# DDR3A.net
KiCad netlist of a schematic drawn in Altium Designer
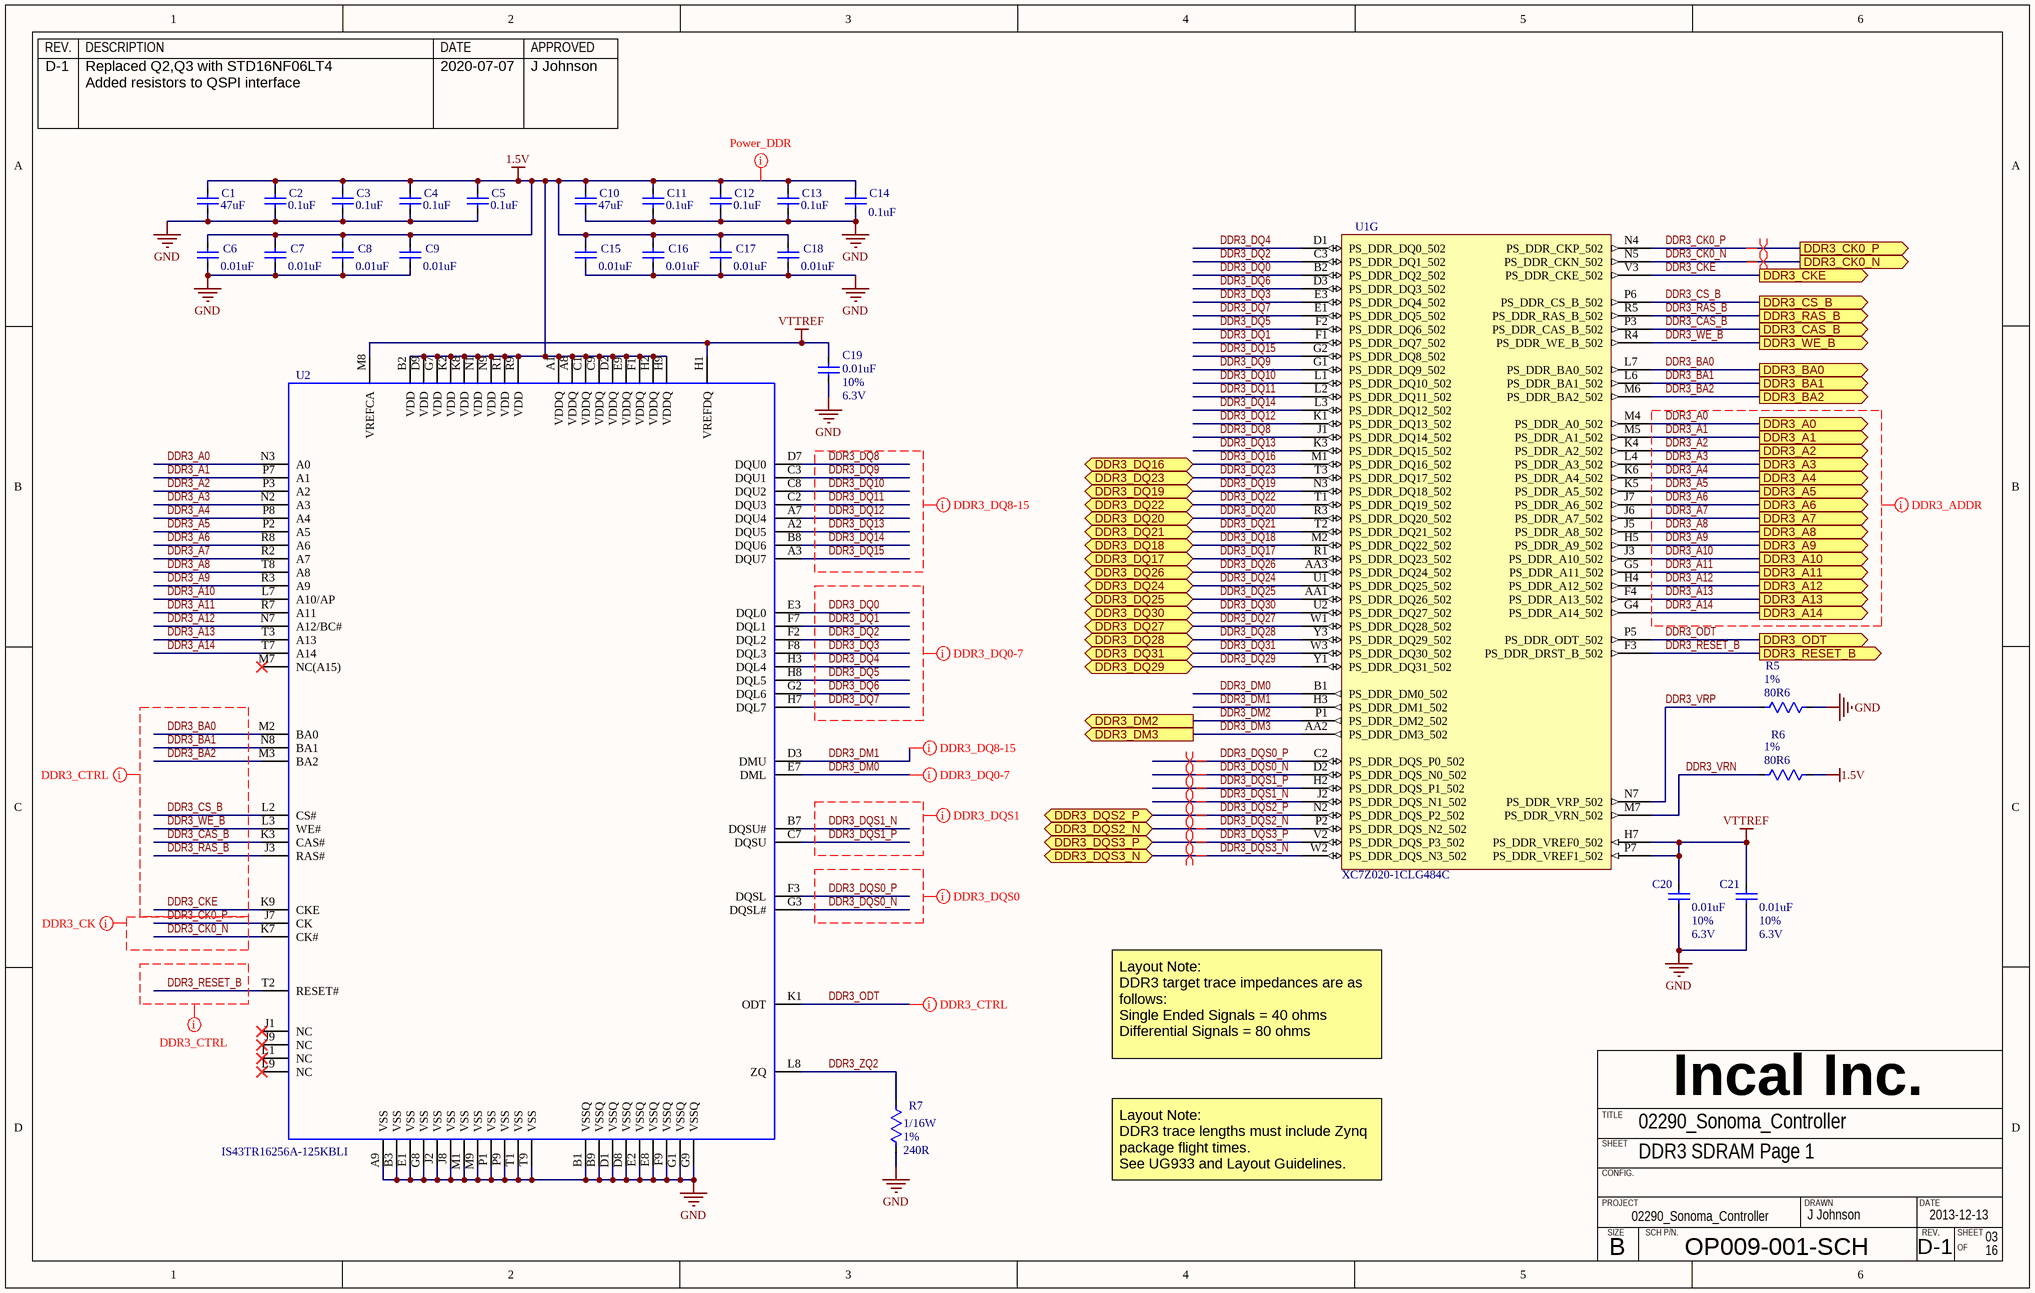
[diagram p0: DDR3A.SchDoc]

(export (version "E")
  (design (tool "Eeschema 10.0.6"))
  (components
    (comp (ref "C1")
      (value "47uF")
      (footprint "CAPC2013X125N")
      (description "Capacitor ceramic, X5R, 47uF, 6.3V, 20%, -55 to +85 C,")
      (fields (field (name "TOLERANCE") "20%") (field (name "VOLTAGE") "6.3V"))
      (libsource (lib "parts") (part "CAPACITOR_NP_TYPE1"))
    )
    (comp (ref "C2")
      (value "0.1uF")
      (footprint "CAPC0603X33N")
      (description "Capacitor ceramic, X5R, 0.1uF, 6.3V, 10%, -55 to +125 C, EIA0201")
      (fields (field (name "TOLERANCE") "10%") (field (name "VOLTAGE") "6.3V"))
      (libsource (lib "parts") (part "CAPACITOR_NP_TYPE1"))
    )
    (comp (ref "C3")
      (value "0.1uF")
      (footprint "CAPC0603X33N")
      (description "Capacitor ceramic, X5R, 0.1uF, 6.3V, 10%, -55 to +125 C, EIA0201")
      (fields (field (name "TOLERANCE") "10%") (field (name "VOLTAGE") "6.3V"))
      (libsource (lib "parts") (part "CAPACITOR_NP_TYPE1"))
    )
    (comp (ref "C4")
      (value "0.1uF")
      (footprint "CAPC0603X33N")
      (description "Capacitor ceramic, X5R, 0.1uF, 6.3V, 10%, -55 to +125 C, EIA0201")
      (fields (field (name "TOLERANCE") "10%") (field (name "VOLTAGE") "6.3V"))
      (libsource (lib "parts") (part "CAPACITOR_NP_TYPE1"))
    )
    (comp (ref "C5")
      (value "0.1uF")
      (footprint "CAPC0603X33N")
      (description "Capacitor ceramic, X5R, 0.1uF, 6.3V, 10%, -55 to +125 C, EIA0201")
      (fields (field (name "TOLERANCE") "10%") (field (name "VOLTAGE") "6.3V"))
      (libsource (lib "parts") (part "CAPACITOR_NP_TYPE1"))
    )
    (comp (ref "C6")
      (value "0.01uF")
      (footprint "CAPC0603X33N")
      (description "Capacitor ceramic, X5R, 0.01uF, 6.3V, 10%, -55 to +125 C, EIA0201")
      (fields (field (name "TOLERANCE") "10%") (field (name "VOLTAGE") "6.3V"))
      (libsource (lib "parts") (part "CAPACITOR_NP_TYPE1"))
    )
    (comp (ref "C7")
      (value "0.01uF")
      (footprint "CAPC0603X33N")
      (description "Capacitor ceramic, X5R, 0.01uF, 6.3V, 10%, -55 to +125 C, EIA0201")
      (fields (field (name "TOLERANCE") "10%") (field (name "VOLTAGE") "6.3V"))
      (libsource (lib "parts") (part "CAPACITOR_NP_TYPE1"))
    )
    (comp (ref "C8")
      (value "0.01uF")
      (footprint "CAPC0603X33N")
      (description "Capacitor ceramic, X5R, 0.01uF, 6.3V, 10%, -55 to +125 C, EIA0201")
      (fields (field (name "TOLERANCE") "10%") (field (name "VOLTAGE") "6.3V"))
      (libsource (lib "parts") (part "CAPACITOR_NP_TYPE1"))
    )
    (comp (ref "C9")
      (value "0.01uF")
      (footprint "CAPC0603X33N")
      (description "Capacitor ceramic, X5R, 0.01uF, 6.3V, 10%, -55 to +125 C, EIA0201")
      (fields (field (name "TOLERANCE") "10%") (field (name "VOLTAGE") "6.3V"))
      (libsource (lib "parts") (part "CAPACITOR_NP_TYPE1"))
    )
    (comp (ref "C10")
      (value "47uF")
      (footprint "CAPC2013X125N")
      (description "Capacitor ceramic, X5R, 47uF, 6.3V, 20%, -55 to +85 C,")
      (fields (field (name "TOLERANCE") "20%") (field (name "VOLTAGE") "6.3V"))
      (libsource (lib "parts") (part "CAPACITOR_NP_TYPE1"))
    )
    (comp (ref "C11")
      (value "0.1uF")
      (footprint "CAPC0603X33N")
      (description "Capacitor ceramic, X5R, 0.1uF, 6.3V, 10%, -55 to +125 C, EIA0201")
      (fields (field (name "TOLERANCE") "10%") (field (name "VOLTAGE") "6.3V"))
      (libsource (lib "parts") (part "CAPACITOR_NP_TYPE1"))
    )
    (comp (ref "C12")
      (value "0.1uF")
      (footprint "CAPC0603X33N")
      (description "Capacitor ceramic, X5R, 0.1uF, 6.3V, 10%, -55 to +125 C, EIA0201")
      (fields (field (name "TOLERANCE") "10%") (field (name "VOLTAGE") "6.3V"))
      (libsource (lib "parts") (part "CAPACITOR_NP_TYPE1"))
    )
    (comp (ref "C13")
      (value "0.1uF")
      (footprint "CAPC0603X33N")
      (description "Capacitor ceramic, X5R, 0.1uF, 6.3V, 10%, -55 to +125 C, EIA0201")
      (fields (field (name "TOLERANCE") "10%") (field (name "VOLTAGE") "6.3V"))
      (libsource (lib "parts") (part "CAPACITOR_NP_TYPE1"))
    )
    (comp (ref "C14")
      (value "0.1uF")
      (footprint "CAPC0603X33N")
      (description "Capacitor ceramic, X5R, 0.1uF, 6.3V, 10%, -55 to +125 C, EIA0201")
      (fields (field (name "TOLERANCE") "10%") (field (name "VOLTAGE") "6.3V"))
      (libsource (lib "parts") (part "CAPACITOR_NP_TYPE1"))
    )
    (comp (ref "C15")
      (value "0.01uF")
      (footprint "CAPC0603X33N")
      (description "Capacitor ceramic, X5R, 0.01uF, 6.3V, 10%, -55 to +125 C, EIA0201")
      (fields (field (name "TOLERANCE") "10%") (field (name "VOLTAGE") "6.3V"))
      (libsource (lib "parts") (part "CAPACITOR_NP_TYPE1"))
    )
    (comp (ref "C16")
      (value "0.01uF")
      (footprint "CAPC0603X33N")
      (description "Capacitor ceramic, X5R, 0.01uF, 6.3V, 10%, -55 to +125 C, EIA0201")
      (fields (field (name "TOLERANCE") "10%") (field (name "VOLTAGE") "6.3V"))
      (libsource (lib "parts") (part "CAPACITOR_NP_TYPE1"))
    )
    (comp (ref "C17")
      (value "0.01uF")
      (footprint "CAPC0603X33N")
      (description "Capacitor ceramic, X5R, 0.01uF, 6.3V, 10%, -55 to +125 C, EIA0201")
      (fields (field (name "TOLERANCE") "10%") (field (name "VOLTAGE") "6.3V"))
      (libsource (lib "parts") (part "CAPACITOR_NP_TYPE1"))
    )
    (comp (ref "C18")
      (value "0.01uF")
      (footprint "CAPC0603X33N")
      (description "Capacitor ceramic, X5R, 0.01uF, 6.3V, 10%, -55 to +125 C, EIA0201")
      (fields (field (name "TOLERANCE") "10%") (field (name "VOLTAGE") "6.3V"))
      (libsource (lib "parts") (part "CAPACITOR_NP_TYPE1"))
    )
    (comp (ref "C19")
      (value "0.01uF")
      (footprint "CAPC0603X33N")
      (description "Capacitor ceramic, X5R, 0.01uF, 6.3V, 10%, -55 to +125 C, EIA0201")
      (fields
        (field (name "TOLERANCE") "10%")
        (field (name "VOLTAGE") "6.3V")
        (field (name "Comment") "CAPACITOR_NP_TYPE1")
      )
      (libsource (lib "parts") (part "CAPACITOR_NP_TYPE1"))
    )
    (comp (ref "C20")
      (value "0.01uF")
      (footprint "CAPC0603X33N")
      (description "Capacitor ceramic, X5R, 0.01uF, 6.3V, 10%, -55 to +125 C, EIA0201")
      (fields
        (field (name "TOLERANCE") "10%")
        (field (name "VOLTAGE") "6.3V")
        (field (name "Comment") "CAPACITOR_NP_TYPE1")
      )
      (libsource (lib "parts") (part "CAPACITOR_NP_TYPE1"))
    )
    (comp (ref "C21")
      (value "0.01uF")
      (footprint "CAPC0603X33N")
      (description "Capacitor ceramic, X5R, 0.01uF, 6.3V, 10%, -55 to +125 C, EIA0201")
      (fields
        (field (name "TOLERANCE") "10%")
        (field (name "VOLTAGE") "6.3V")
        (field (name "Comment") "CAPACITOR_NP_TYPE1")
      )
      (libsource (lib "parts") (part "CAPACITOR_NP_TYPE1"))
    )
    (comp (ref "R5")
      (value "80R6")
      (footprint "RESC1005X33N")
      (description "Resistor, 80R6, 1/16W, 1%, -50 to +155 C, EIA0402, EIA(M)1005")
      (fields (field (name "VOLTAGE") "50V") (field (name "POWER") "1/16W") (field (name "TOLERANCE") "1%"))
      (libsource (lib "parts") (part "RESISTOR_TYPE1"))
    )
    (comp (ref "R6")
      (value "80R6")
      (footprint "RESC1005X33N")
      (description "Resistor, 80R6, 1/16W, 1%, -50 to +155 C, EIA0402, EIA(M)1005")
      (fields (field (name "VOLTAGE") "50V") (field (name "POWER") "1/16W") (field (name "TOLERANCE") "1%"))
      (libsource (lib "parts") (part "RESISTOR_TYPE1"))
    )
    (comp (ref "R7")
      (value "240R")
      (footprint "RESC1005X33N")
      (description "Resistor, 240R, 1/16W, 1%, -50 to +155 C, EIA0402, EIA(M)1005")
      (fields (field (name "VOLTAGE") "50V") (field (name "POWER") "1/16W") (field (name "TOLERANCE") "1%"))
      (libsource (lib "parts") (part "RESISTOR_TYPE1"))
    )
    (comp (ref "U1")
      (value "XC7Z020-1CLG484C")
      (footprint "CLG484")
      (description "667 MHz Zynq™-7000 AP SoC, 130 PS I/O, 200 FPGA I/O, 484-Ball BGA, Speed Grade 1, Commercial Grade")
      (fields (field (name "GENERIC PART NUMBER") "XC7Z020") (field (name "MANUFACTURER") "Xilinx"))
      (libsource (lib "parts") (part "XC7Z020-1CLG484C"))
    )
    (comp (ref "U2")
      (value "IS43TR16256A-125KBLI")
      (footprint "BGA96C80P6X16_900X1300X120")
      (description "DDR3 SDRAM, 512Mx8, 256Mx16 4Gb")
      (libsource (lib "parts") (part "IS43TR16256A-125KBLI"))
    )
  )
  (nets
    (net (code "1") (name "/DDR3_A0") (class "Default")
      (node (ref "U1") (pin "M4") (pinfunction "PS_DDR_A0_502_M4") (pintype "output"))
      (node (ref "U2") (pin "N3") (pinfunction "A0_N3") (pintype "passive"))
    )
    (net (code "2") (name "/DDR3_A1") (class "Default")
      (node (ref "U1") (pin "M5") (pinfunction "PS_DDR_A1_502_M5") (pintype "output"))
      (node (ref "U2") (pin "P7") (pinfunction "A1_P7") (pintype "passive"))
    )
    (net (code "3") (name "/DDR3_A2") (class "Default")
      (node (ref "U1") (pin "K4") (pinfunction "PS_DDR_A2_502_K4") (pintype "output"))
      (node (ref "U2") (pin "P3") (pinfunction "A2_P3") (pintype "passive"))
    )
    (net (code "4") (name "/DDR3_A3") (class "Default")
      (node (ref "U1") (pin "L4") (pinfunction "PS_DDR_A3_502_L4") (pintype "output"))
      (node (ref "U2") (pin "N2") (pinfunction "A3_N2") (pintype "passive"))
    )
    (net (code "5") (name "/DDR3_A4") (class "Default")
      (node (ref "U1") (pin "K6") (pinfunction "PS_DDR_A4_502_K6") (pintype "output"))
      (node (ref "U2") (pin "P8") (pinfunction "A4_P8") (pintype "passive"))
    )
    (net (code "6") (name "/DDR3_A5") (class "Default")
      (node (ref "U1") (pin "K5") (pinfunction "PS_DDR_A5_502_K5") (pintype "output"))
      (node (ref "U2") (pin "P2") (pinfunction "A5_P2") (pintype "passive"))
    )
    (net (code "7") (name "/DDR3_A6") (class "Default")
      (node (ref "U1") (pin "J7") (pinfunction "PS_DDR_A6_502_J7") (pintype "output"))
      (node (ref "U2") (pin "R8") (pinfunction "A6_R8") (pintype "passive"))
    )
    (net (code "8") (name "/DDR3_A7") (class "Default")
      (node (ref "U1") (pin "J6") (pinfunction "PS_DDR_A7_502_J6") (pintype "output"))
      (node (ref "U2") (pin "R2") (pinfunction "A7_R2") (pintype "passive"))
    )
    (net (code "9") (name "/DDR3_A8") (class "Default")
      (node (ref "U1") (pin "J5") (pinfunction "PS_DDR_A8_502_J5") (pintype "output"))
      (node (ref "U2") (pin "T8") (pinfunction "A8_T8") (pintype "passive"))
    )
    (net (code "10") (name "/DDR3_A9") (class "Default")
      (node (ref "U1") (pin "H5") (pinfunction "PS_DDR_A9_502_H5") (pintype "output"))
      (node (ref "U2") (pin "R3") (pinfunction "A9_R3") (pintype "passive"))
    )
    (net (code "11") (name "/DDR3_A10") (class "Default")
      (node (ref "U1") (pin "J3") (pinfunction "PS_DDR_A10_502_J3") (pintype "output"))
      (node (ref "U2") (pin "L7") (pinfunction "A10/AP_L7") (pintype "passive"))
    )
    (net (code "12") (name "/DDR3_A11") (class "Default")
      (node (ref "U1") (pin "G5") (pinfunction "PS_DDR_A11_502_G5") (pintype "output"))
      (node (ref "U2") (pin "R7") (pinfunction "A11_R7") (pintype "passive"))
    )
    (net (code "13") (name "/DDR3_A12") (class "Default")
      (node (ref "U1") (pin "H4") (pinfunction "PS_DDR_A12_502_H4") (pintype "output"))
      (node (ref "U2") (pin "N7") (pinfunction "A12/BC#_N7") (pintype "passive"))
    )
    (net (code "14") (name "/DDR3_A13") (class "Default")
      (node (ref "U1") (pin "F4") (pinfunction "PS_DDR_A13_502_F4") (pintype "output"))
      (node (ref "U2") (pin "T3") (pinfunction "A13_T3") (pintype "passive"))
    )
    (net (code "15") (name "/DDR3_A14") (class "Default")
      (node (ref "U1") (pin "G4") (pinfunction "PS_DDR_A14_502_G4") (pintype "output"))
      (node (ref "U2") (pin "T7") (pinfunction "A14_T7") (pintype "passive"))
    )
    (net (code "16") (name "/DDR3_BA0") (class "Default")
      (node (ref "U1") (pin "L7") (pinfunction "PS_DDR_BA0_502_L7") (pintype "output"))
      (node (ref "U2") (pin "M2") (pinfunction "BA0_M2") (pintype "passive"))
    )
    (net (code "17") (name "/DDR3_BA1") (class "Default")
      (node (ref "U1") (pin "L6") (pinfunction "PS_DDR_BA1_502_L6") (pintype "output"))
      (node (ref "U2") (pin "N8") (pinfunction "BA1_N8") (pintype "passive"))
    )
    (net (code "18") (name "/DDR3_BA2") (class "Default")
      (node (ref "U1") (pin "M6") (pinfunction "PS_DDR_BA2_502_M6") (pintype "output"))
      (node (ref "U2") (pin "M3") (pinfunction "BA2_M3") (pintype "passive"))
    )
    (net (code "19") (name "/DDR3_CAS_B") (class "Default")
      (node (ref "U1") (pin "P3") (pinfunction "PS_DDR_CAS_B_502_P3") (pintype "output"))
      (node (ref "U2") (pin "K3") (pinfunction "CAS#_K3") (pintype "passive"))
    )
    (net (code "20") (name "/DDR3_CK0_N") (class "Default")
      (node (ref "U1") (pin "N5") (pinfunction "PS_DDR_CKN_502_N5") (pintype "output"))
      (node (ref "U2") (pin "K7") (pinfunction "CK#_K7") (pintype "passive"))
    )
    (net (code "21") (name "/DDR3_CK0_P") (class "Default")
      (node (ref "U1") (pin "N4") (pinfunction "PS_DDR_CKP_502_N4") (pintype "output"))
      (node (ref "U2") (pin "J7") (pinfunction "CK_J7") (pintype "passive"))
    )
    (net (code "22") (name "/DDR3_CKE") (class "Default")
      (node (ref "U1") (pin "V3") (pinfunction "PS_DDR_CKE_502_V3") (pintype "output"))
      (node (ref "U2") (pin "K9") (pinfunction "CKE_K9") (pintype "passive"))
    )
    (net (code "23") (name "/DDR3_CS_B") (class "Default")
      (node (ref "U1") (pin "P6") (pinfunction "PS_DDR_CS_B_502_P6") (pintype "output"))
      (node (ref "U2") (pin "L2") (pinfunction "CS#_L2") (pintype "passive"))
    )
    (net (code "24") (name "/DDR3_DM0") (class "Default")
      (node (ref "U1") (pin "B1") (pinfunction "PS_DDR_DM0_502_B1") (pintype "output"))
      (node (ref "U2") (pin "E7") (pinfunction "DML_E7") (pintype "passive"))
    )
    (net (code "25") (name "/DDR3_DM1") (class "Default")
      (node (ref "U1") (pin "H3") (pinfunction "PS_DDR_DM1_502_H3") (pintype "output"))
      (node (ref "U2") (pin "D3") (pinfunction "DMU_D3") (pintype "passive"))
    )
    (net (code "26") (name "/DDR3_DM2") (class "Default")
      (node (ref "U1") (pin "P1") (pinfunction "PS_DDR_DM2_502_P1") (pintype "output"))
    )
    (net (code "27") (name "/DDR3_DM3") (class "Default")
      (node (ref "U1") (pin "AA2") (pinfunction "PS_DDR_DM3_502_AA2") (pintype "output"))
    )
    (net (code "28") (name "/DDR3_DQ0") (class "Default")
      (node (ref "U1") (pin "B2") (pinfunction "PS_DDR_DQ2_502_B2") (pintype "bidirectional"))
      (node (ref "U2") (pin "E3") (pinfunction "DQL0_E3") (pintype "passive"))
    )
    (net (code "29") (name "/DDR3_DQ1") (class "Default")
      (node (ref "U1") (pin "F1") (pinfunction "PS_DDR_DQ7_502_F1") (pintype "bidirectional"))
      (node (ref "U2") (pin "F7") (pinfunction "DQL1_F7") (pintype "passive"))
    )
    (net (code "30") (name "/DDR3_DQ2") (class "Default")
      (node (ref "U1") (pin "C3") (pinfunction "PS_DDR_DQ1_502_C3") (pintype "bidirectional"))
      (node (ref "U2") (pin "F2") (pinfunction "DQL2_F2") (pintype "passive"))
    )
    (net (code "31") (name "/DDR3_DQ3") (class "Default")
      (node (ref "U1") (pin "E3") (pinfunction "PS_DDR_DQ4_502_E3") (pintype "bidirectional"))
      (node (ref "U2") (pin "F8") (pinfunction "DQL3_F8") (pintype "passive"))
    )
    (net (code "32") (name "/DDR3_DQ4") (class "Default")
      (node (ref "U1") (pin "D1") (pinfunction "PS_DDR_DQ0_502_D1") (pintype "bidirectional"))
      (node (ref "U2") (pin "H3") (pinfunction "DQL4_H3") (pintype "passive"))
    )
    (net (code "33") (name "/DDR3_DQ5") (class "Default")
      (node (ref "U1") (pin "F2") (pinfunction "PS_DDR_DQ6_502_F2") (pintype "bidirectional"))
      (node (ref "U2") (pin "H8") (pinfunction "DQL5_H8") (pintype "passive"))
    )
    (net (code "34") (name "/DDR3_DQ6") (class "Default")
      (node (ref "U1") (pin "D3") (pinfunction "PS_DDR_DQ3_502_D3") (pintype "bidirectional"))
      (node (ref "U2") (pin "G2") (pinfunction "DQL6_G2") (pintype "passive"))
    )
    (net (code "35") (name "/DDR3_DQ7") (class "Default")
      (node (ref "U1") (pin "E1") (pinfunction "PS_DDR_DQ5_502_E1") (pintype "bidirectional"))
      (node (ref "U2") (pin "H7") (pinfunction "DQL7_H7") (pintype "passive"))
    )
    (net (code "36") (name "/DDR3_DQ8") (class "Default")
      (node (ref "U1") (pin "J1") (pinfunction "PS_DDR_DQ14_502_J1") (pintype "bidirectional"))
      (node (ref "U2") (pin "D7") (pinfunction "DQU0_D7") (pintype "passive"))
    )
    (net (code "37") (name "/DDR3_DQ9") (class "Default")
      (node (ref "U1") (pin "G1") (pinfunction "PS_DDR_DQ9_502_G1") (pintype "bidirectional"))
      (node (ref "U2") (pin "C3") (pinfunction "DQU1_C3") (pintype "passive"))
    )
    (net (code "38") (name "/DDR3_DQ10") (class "Default")
      (node (ref "U1") (pin "L1") (pinfunction "PS_DDR_DQ10_502_L1") (pintype "bidirectional"))
      (node (ref "U2") (pin "C8") (pinfunction "DQU2_C8") (pintype "passive"))
    )
    (net (code "39") (name "/DDR3_DQ11") (class "Default")
      (node (ref "U1") (pin "L2") (pinfunction "PS_DDR_DQ11_502_L2") (pintype "bidirectional"))
      (node (ref "U2") (pin "C2") (pinfunction "DQU3_C2") (pintype "passive"))
    )
    (net (code "40") (name "/DDR3_DQ12") (class "Default")
      (node (ref "U1") (pin "K1") (pinfunction "PS_DDR_DQ13_502_K1") (pintype "bidirectional"))
      (node (ref "U2") (pin "A7") (pinfunction "DQU4_A7") (pintype "passive"))
    )
    (net (code "41") (name "/DDR3_DQ13") (class "Default")
      (node (ref "U1") (pin "K3") (pinfunction "PS_DDR_DQ15_502_K3") (pintype "bidirectional"))
      (node (ref "U2") (pin "A2") (pinfunction "DQU5_A2") (pintype "passive"))
    )
    (net (code "42") (name "/DDR3_DQ14") (class "Default")
      (node (ref "U1") (pin "L3") (pinfunction "PS_DDR_DQ12_502_L3") (pintype "bidirectional"))
      (node (ref "U2") (pin "B8") (pinfunction "DQU6_B8") (pintype "passive"))
    )
    (net (code "43") (name "/DDR3_DQ15") (class "Default")
      (node (ref "U1") (pin "G2") (pinfunction "PS_DDR_DQ8_502_G2") (pintype "bidirectional"))
      (node (ref "U2") (pin "A3") (pinfunction "DQU7_A3") (pintype "passive"))
    )
    (net (code "44") (name "/DDR3_DQ16") (class "Default")
      (node (ref "U1") (pin "M1") (pinfunction "PS_DDR_DQ16_502_M1") (pintype "bidirectional"))
    )
    (net (code "45") (name "/DDR3_DQ17") (class "Default")
      (node (ref "U1") (pin "R1") (pinfunction "PS_DDR_DQ23_502_R1") (pintype "bidirectional"))
    )
    (net (code "46") (name "/DDR3_DQ18") (class "Default")
      (node (ref "U1") (pin "M2") (pinfunction "PS_DDR_DQ22_502_M2") (pintype "bidirectional"))
    )
    (net (code "47") (name "/DDR3_DQ19") (class "Default")
      (node (ref "U1") (pin "N3") (pinfunction "PS_DDR_DQ18_502_N3") (pintype "bidirectional"))
    )
    (net (code "48") (name "/DDR3_DQ20") (class "Default")
      (node (ref "U1") (pin "R3") (pinfunction "PS_DDR_DQ20_502_R3") (pintype "bidirectional"))
    )
    (net (code "49") (name "/DDR3_DQ21") (class "Default")
      (node (ref "U1") (pin "T2") (pinfunction "PS_DDR_DQ21_502_T2") (pintype "bidirectional"))
    )
    (net (code "50") (name "/DDR3_DQ22") (class "Default")
      (node (ref "U1") (pin "T1") (pinfunction "PS_DDR_DQ19_502_T1") (pintype "bidirectional"))
    )
    (net (code "51") (name "/DDR3_DQ23") (class "Default")
      (node (ref "U1") (pin "T3") (pinfunction "PS_DDR_DQ17_502_T3") (pintype "bidirectional"))
    )
    (net (code "52") (name "/DDR3_DQ24") (class "Default")
      (node (ref "U1") (pin "U1") (pinfunction "PS_DDR_DQ25_502_U1") (pintype "bidirectional"))
    )
    (net (code "53") (name "/DDR3_DQ25") (class "Default")
      (node (ref "U1") (pin "AA1") (pinfunction "PS_DDR_DQ26_502_AA1") (pintype "bidirectional"))
    )
    (net (code "54") (name "/DDR3_DQ26") (class "Default")
      (node (ref "U1") (pin "AA3") (pinfunction "PS_DDR_DQ24_502_AA3") (pintype "bidirectional"))
    )
    (net (code "55") (name "/DDR3_DQ27") (class "Default")
      (node (ref "U1") (pin "W1") (pinfunction "PS_DDR_DQ28_502_W1") (pintype "bidirectional"))
    )
    (net (code "56") (name "/DDR3_DQ28") (class "Default")
      (node (ref "U1") (pin "Y3") (pinfunction "PS_DDR_DQ29_502_Y3") (pintype "bidirectional"))
    )
    (net (code "57") (name "/DDR3_DQ29") (class "Default")
      (node (ref "U1") (pin "Y1") (pinfunction "PS_DDR_DQ31_502_Y1") (pintype "bidirectional"))
    )
    (net (code "58") (name "/DDR3_DQ30") (class "Default")
      (node (ref "U1") (pin "U2") (pinfunction "PS_DDR_DQ27_502_U2") (pintype "bidirectional"))
    )
    (net (code "59") (name "/DDR3_DQ31") (class "Default")
      (node (ref "U1") (pin "W3") (pinfunction "PS_DDR_DQ30_502_W3") (pintype "bidirectional"))
    )
    (net (code "60") (name "/DDR3_DQS0_N") (class "Default")
      (node (ref "U1") (pin "D2") (pinfunction "PS_DDR_DQS_N0_502_D2") (pintype "bidirectional"))
      (node (ref "U2") (pin "G3") (pinfunction "DQSL#_G3") (pintype "passive"))
    )
    (net (code "61") (name "/DDR3_DQS0_P") (class "Default")
      (node (ref "U1") (pin "C2") (pinfunction "PS_DDR_DQS_P0_502_C2") (pintype "bidirectional"))
      (node (ref "U2") (pin "F3") (pinfunction "DQSL_F3") (pintype "passive"))
    )
    (net (code "62") (name "/DDR3_DQS1_N") (class "Default")
      (node (ref "U1") (pin "J2") (pinfunction "PS_DDR_DQS_N1_502_J2") (pintype "bidirectional"))
      (node (ref "U2") (pin "B7") (pinfunction "DQSU#_B7") (pintype "passive"))
    )
    (net (code "63") (name "/DDR3_DQS1_P") (class "Default")
      (node (ref "U1") (pin "H2") (pinfunction "PS_DDR_DQS_P1_502_H2") (pintype "bidirectional"))
      (node (ref "U2") (pin "C7") (pinfunction "DQSU_C7") (pintype "passive"))
    )
    (net (code "64") (name "/DDR3_DQS2_N") (class "Default")
      (node (ref "U1") (pin "P2") (pinfunction "PS_DDR_DQS_N2_502_P2") (pintype "bidirectional"))
    )
    (net (code "65") (name "/DDR3_DQS2_P") (class "Default")
      (node (ref "U1") (pin "N2") (pinfunction "PS_DDR_DQS_P2_502_N2") (pintype "bidirectional"))
    )
    (net (code "66") (name "/DDR3_DQS3_N") (class "Default")
      (node (ref "U1") (pin "W2") (pinfunction "PS_DDR_DQS_N3_502_W2") (pintype "bidirectional"))
    )
    (net (code "67") (name "/DDR3_DQS3_P") (class "Default")
      (node (ref "U1") (pin "V2") (pinfunction "PS_DDR_DQS_P3_502_V2") (pintype "bidirectional"))
    )
    (net (code "68") (name "/DDR3_ODT") (class "Default")
      (node (ref "U1") (pin "P5") (pinfunction "PS_DDR_ODT_502_P5") (pintype "output"))
      (node (ref "U2") (pin "K1") (pinfunction "ODT_K1") (pintype "passive"))
    )
    (net (code "69") (name "/DDR3_RAS_B") (class "Default")
      (node (ref "U1") (pin "R5") (pinfunction "PS_DDR_RAS_B_502_R5") (pintype "output"))
      (node (ref "U2") (pin "J3") (pinfunction "RAS#_J3") (pintype "passive"))
    )
    (net (code "70") (name "/DDR3_RESET_B") (class "Default")
      (node (ref "U1") (pin "F3") (pinfunction "PS_DDR_DRST_B_502_F3") (pintype "output"))
      (node (ref "U2") (pin "T2") (pinfunction "RESET#_T2") (pintype "passive"))
    )
    (net (code "71") (name "/DDR3_VRN") (class "Default")
      (node (ref "R6") (pin "2") (pinfunction "2_2") (pintype "passive"))
      (node (ref "U1") (pin "M7") (pinfunction "PS_DDR_VRN_502_M7") (pintype "output"))
    )
    (net (code "72") (name "/DDR3_VRP") (class "Default")
      (node (ref "R5") (pin "1") (pinfunction "1_1") (pintype "passive"))
      (node (ref "U1") (pin "N7") (pinfunction "PS_DDR_VRP_502_N7") (pintype "output"))
    )
    (net (code "73") (name "/DDR3_WE_B") (class "Default")
      (node (ref "U1") (pin "R4") (pinfunction "PS_DDR_WE_B_502_R4") (pintype "output"))
      (node (ref "U2") (pin "L3") (pinfunction "WE#_L3") (pintype "passive"))
    )
    (net (code "74") (name "/DDR3_ZQ2") (class "Default")
      (node (ref "R7") (pin "2") (pinfunction "2_2") (pintype "passive"))
      (node (ref "U2") (pin "L8") (pinfunction "ZQ_L8") (pintype "passive"))
    )
    (net (code "75") (name "1.5V") (class "Default")
      (node (ref "C1") (pin "1") (pinfunction "1_1") (pintype "passive"))
      (node (ref "C10") (pin "1") (pinfunction "1_1") (pintype "passive"))
      (node (ref "C11") (pin "1") (pinfunction "1_1") (pintype "passive"))
      (node (ref "C12") (pin "1") (pinfunction "1_1") (pintype "passive"))
      (node (ref "C13") (pin "1") (pinfunction "1_1") (pintype "passive"))
      (node (ref "C14") (pin "1") (pinfunction "1_1") (pintype "passive"))
      (node (ref "C15") (pin "1") (pinfunction "1_1") (pintype "passive"))
      (node (ref "C16") (pin "1") (pinfunction "1_1") (pintype "passive"))
      (node (ref "C17") (pin "1") (pinfunction "1_1") (pintype "passive"))
      (node (ref "C18") (pin "1") (pinfunction "1_1") (pintype "passive"))
      (node (ref "C2") (pin "1") (pinfunction "1_1") (pintype "passive"))
      (node (ref "C3") (pin "1") (pinfunction "1_1") (pintype "passive"))
      (node (ref "C4") (pin "1") (pinfunction "1_1") (pintype "passive"))
      (node (ref "C5") (pin "1") (pinfunction "1_1") (pintype "passive"))
      (node (ref "C6") (pin "1") (pinfunction "1_1") (pintype "passive"))
      (node (ref "C7") (pin "1") (pinfunction "1_1") (pintype "passive"))
      (node (ref "C8") (pin "1") (pinfunction "1_1") (pintype "passive"))
      (node (ref "C9") (pin "1") (pinfunction "1_1") (pintype "passive"))
      (node (ref "R6") (pin "1") (pinfunction "1_1") (pintype "passive"))
      (node (ref "U2") (pin "A1") (pinfunction "VDDQ_A1") (pintype "passive"))
      (node (ref "U2") (pin "A8") (pinfunction "VDDQ_A8") (pintype "passive"))
      (node (ref "U2") (pin "B2") (pinfunction "VDD_B2") (pintype "passive"))
      (node (ref "U2") (pin "C1") (pinfunction "VDDQ_C1") (pintype "passive"))
      (node (ref "U2") (pin "C9") (pinfunction "VDDQ_C9") (pintype "passive"))
      (node (ref "U2") (pin "D2") (pinfunction "VDDQ_D2") (pintype "passive"))
      (node (ref "U2") (pin "D9") (pinfunction "VDD_D9") (pintype "passive"))
      (node (ref "U2") (pin "E9") (pinfunction "VDDQ_E9") (pintype "passive"))
      (node (ref "U2") (pin "F1") (pinfunction "VDDQ_F1") (pintype "passive"))
      (node (ref "U2") (pin "G7") (pinfunction "VDD_G7") (pintype "passive"))
      (node (ref "U2") (pin "H2") (pinfunction "VDDQ_H2") (pintype "passive"))
      (node (ref "U2") (pin "H9") (pinfunction "VDDQ_H9") (pintype "passive"))
      (node (ref "U2") (pin "K2") (pinfunction "VDD_K2") (pintype "passive"))
      (node (ref "U2") (pin "K8") (pinfunction "VDD_K8") (pintype "passive"))
      (node (ref "U2") (pin "N1") (pinfunction "VDD_N1") (pintype "passive"))
      (node (ref "U2") (pin "N9") (pinfunction "VDD_N9") (pintype "passive"))
      (node (ref "U2") (pin "R1") (pinfunction "VDD_R1") (pintype "passive"))
      (node (ref "U2") (pin "R9") (pinfunction "VDD_R9") (pintype "passive"))
    )
    (net (code "76") (name "GND") (class "Default")
      (node (ref "C1") (pin "2") (pinfunction "2_2") (pintype "passive"))
      (node (ref "C10") (pin "2") (pinfunction "2_2") (pintype "passive"))
      (node (ref "C11") (pin "2") (pinfunction "2_2") (pintype "passive"))
      (node (ref "C12") (pin "2") (pinfunction "2_2") (pintype "passive"))
      (node (ref "C13") (pin "2") (pinfunction "2_2") (pintype "passive"))
      (node (ref "C14") (pin "2") (pinfunction "2_2") (pintype "passive"))
      (node (ref "C15") (pin "2") (pinfunction "2_2") (pintype "passive"))
      (node (ref "C16") (pin "2") (pinfunction "2_2") (pintype "passive"))
      (node (ref "C17") (pin "2") (pinfunction "2_2") (pintype "passive"))
      (node (ref "C18") (pin "2") (pinfunction "2_2") (pintype "passive"))
      (node (ref "C19") (pin "2") (pinfunction "2_2") (pintype "passive"))
      (node (ref "C2") (pin "2") (pinfunction "2_2") (pintype "passive"))
      (node (ref "C20") (pin "2") (pinfunction "2_2") (pintype "passive"))
      (node (ref "C21") (pin "2") (pinfunction "2_2") (pintype "passive"))
      (node (ref "C3") (pin "2") (pinfunction "2_2") (pintype "passive"))
      (node (ref "C4") (pin "2") (pinfunction "2_2") (pintype "passive"))
      (node (ref "C5") (pin "2") (pinfunction "2_2") (pintype "passive"))
      (node (ref "C6") (pin "2") (pinfunction "2_2") (pintype "passive"))
      (node (ref "C7") (pin "2") (pinfunction "2_2") (pintype "passive"))
      (node (ref "C8") (pin "2") (pinfunction "2_2") (pintype "passive"))
      (node (ref "C9") (pin "2") (pinfunction "2_2") (pintype "passive"))
      (node (ref "R5") (pin "2") (pinfunction "2_2") (pintype "passive"))
      (node (ref "R7") (pin "1") (pinfunction "1_1") (pintype "passive"))
      (node (ref "U2") (pin "A9") (pinfunction "VSS_A9") (pintype "passive"))
      (node (ref "U2") (pin "B1") (pinfunction "VSSQ_B1") (pintype "passive"))
      (node (ref "U2") (pin "B3") (pinfunction "VSS_B3") (pintype "passive"))
      (node (ref "U2") (pin "B9") (pinfunction "VSSQ_B9") (pintype "passive"))
      (node (ref "U2") (pin "D1") (pinfunction "VSSQ_D1") (pintype "passive"))
      (node (ref "U2") (pin "D8") (pinfunction "VSSQ_D8") (pintype "passive"))
      (node (ref "U2") (pin "E1") (pinfunction "VSS_E1") (pintype "passive"))
      (node (ref "U2") (pin "E2") (pinfunction "VSSQ_E2") (pintype "passive"))
      (node (ref "U2") (pin "E8") (pinfunction "VSSQ_E8") (pintype "passive"))
      (node (ref "U2") (pin "F9") (pinfunction "VSSQ_F9") (pintype "passive"))
      (node (ref "U2") (pin "G1") (pinfunction "VSSQ_G1") (pintype "passive"))
      (node (ref "U2") (pin "G8") (pinfunction "VSS_G8") (pintype "passive"))
      (node (ref "U2") (pin "G9") (pinfunction "VSSQ_G9") (pintype "passive"))
      (node (ref "U2") (pin "J2") (pinfunction "VSS_J2") (pintype "passive"))
      (node (ref "U2") (pin "J8") (pinfunction "VSS_J8") (pintype "passive"))
      (node (ref "U2") (pin "M1") (pinfunction "VSS_M1") (pintype "passive"))
      (node (ref "U2") (pin "M9") (pinfunction "VSS_M9") (pintype "passive"))
      (node (ref "U2") (pin "P1") (pinfunction "VSS_P1") (pintype "passive"))
      (node (ref "U2") (pin "P9") (pinfunction "VSS_P9") (pintype "passive"))
      (node (ref "U2") (pin "T1") (pinfunction "VSS_T1") (pintype "passive"))
      (node (ref "U2") (pin "T9") (pinfunction "VSS_T9") (pintype "passive"))
    )
    (net (code "77") (name "VTTREF") (class "Default")
      (node (ref "C19") (pin "1") (pinfunction "1_1") (pintype "passive"))
      (node (ref "C20") (pin "1") (pinfunction "1_1") (pintype "passive"))
      (node (ref "C21") (pin "1") (pinfunction "1_1") (pintype "passive"))
      (node (ref "U1") (pin "H7") (pinfunction "PS_DDR_VREF0_502_H7") (pintype "input"))
      (node (ref "U1") (pin "P7") (pinfunction "PS_DDR_VREF1_502_P7") (pintype "input"))
      (node (ref "U2") (pin "H1") (pinfunction "VREFDQ_H1") (pintype "passive"))
      (node (ref "U2") (pin "M8") (pinfunction "VREFCA_M8") (pintype "passive"))
    )
    (net (code "78") (name "unconnected-(U2-NC(A15)-PadM7)") (class "Default")
      (node (ref "U2") (pin "M7") (pinfunction "NC(A15)_M7") (pintype "passive+no_connect"))
    )
    (net (code "79") (name "unconnected-(U2-NC-PadJ1)") (class "Default")
      (node (ref "U2") (pin "J1") (pinfunction "NC_J1") (pintype "passive+no_connect"))
    )
    (net (code "80") (name "unconnected-(U2-NC-PadJ9)") (class "Default")
      (node (ref "U2") (pin "J9") (pinfunction "NC_J9") (pintype "passive+no_connect"))
    )
    (net (code "81") (name "unconnected-(U2-NC-PadL1)") (class "Default")
      (node (ref "U2") (pin "L1") (pinfunction "NC_L1") (pintype "passive+no_connect"))
    )
    (net (code "82") (name "unconnected-(U2-NC-PadL9)") (class "Default")
      (node (ref "U2") (pin "L9") (pinfunction "NC_L9") (pintype "passive+no_connect"))
    )
  )
)
